# inv_pendulum.net
KiCad netlist of a schematic drawn in EAGLE
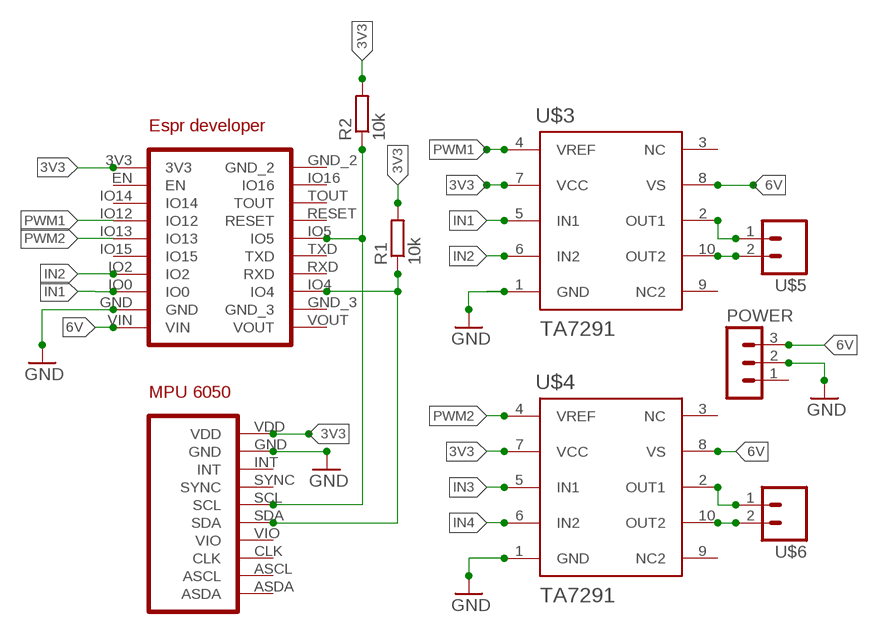
[diagram p0: schematic, sheet 1]

(export (version "E")
  (design (tool "Eeschema 10.0.6"))
  (components
    (comp (ref "POWER")
      (value "MA03-1")
      (footprint "eagle-import:MA03-1")
      (libsource (lib "eagle-import") (part "MA03-1"))
    )
    (comp (ref "R1")
      (value "10k")
      (footprint "eagle-import:0204_7")
      (libsource (lib "eagle-import") (part "R-EU_0204/7"))
    )
    (comp (ref "R2")
      (value "10k")
      (footprint "eagle-import:0204_7")
      (libsource (lib "eagle-import") (part "R-EU_0204/7"))
    )
    (comp (ref "U$1")
      (value "MPU6050")
      (footprint "eagle-import:MPU6050")
      (libsource (lib "eagle-import") (part "MPU6050"))
    )
    (comp (ref "U$2")
      (value "ESPR_DEVELOPER")
      (footprint "eagle-import:ESPR_DEV")
      (libsource (lib "eagle-import") (part "ESPR_DEVELOPER"))
    )
    (comp (ref "U$3")
      (value "TA7291")
      (footprint "eagle-import:HSIP10")
      (libsource (lib "eagle-import") (part "TA7291"))
    )
    (comp (ref "U$4")
      (value "TA7291")
      (footprint "eagle-import:HSIP10")
      (libsource (lib "eagle-import") (part "TA7291"))
    )
    (comp (ref "U$5")
      (value "M02LOCK_LONGPADS")
      (footprint "eagle-import:1X02_LOCK_LONGPADS")
      (libsource (lib "eagle-import") (part "M02LOCK_LONGPADS"))
    )
    (comp (ref "U$6")
      (value "M02LOCK_LONGPADS")
      (footprint "eagle-import:1X02_LOCK_LONGPADS")
      (libsource (lib "eagle-import") (part "M02LOCK_LONGPADS"))
    )
  )
  (nets
    (net (code "1") (name "3V3") (class "Default")
      (node (ref "R1") (pin "2") (pinfunction "2_2") (pintype "passive"))
      (node (ref "R2") (pin "2") (pinfunction "2_2") (pintype "passive"))
      (node (ref "U$1") (pin "VDD") (pinfunction "VDD_VDD") (pintype "bidirectional"))
      (node (ref "U$2") (pin "3V3") (pinfunction "3V3_3V3") (pintype "bidirectional"))
      (node (ref "U$3") (pin "7") (pinfunction "VCC_7") (pintype "bidirectional"))
      (node (ref "U$4") (pin "7") (pinfunction "VCC_7") (pintype "bidirectional"))
    )
    (net (code "2") (name "6V") (class "Default")
      (node (ref "POWER") (pin "3") (pinfunction "3_3") (pintype "passive"))
      (node (ref "U$2") (pin "VIN") (pinfunction "VIN_VIN") (pintype "bidirectional"))
      (node (ref "U$3") (pin "8") (pinfunction "VS_8") (pintype "bidirectional"))
      (node (ref "U$4") (pin "8") (pinfunction "VS_8") (pintype "bidirectional"))
    )
    (net (code "3") (name "GND") (class "Default")
      (node (ref "POWER") (pin "2") (pinfunction "2_2") (pintype "passive"))
      (node (ref "U$1") (pin "GND") (pinfunction "GND_GND") (pintype "bidirectional"))
      (node (ref "U$2") (pin "GND") (pinfunction "GND_GND") (pintype "bidirectional"))
      (node (ref "U$3") (pin "1") (pinfunction "GND_1") (pintype "bidirectional"))
      (node (ref "U$4") (pin "1") (pinfunction "GND_1") (pintype "bidirectional"))
    )
    (net (code "4") (name "IN1") (class "Default")
      (node (ref "U$2") (pin "IO0") (pinfunction "IO0_IO0") (pintype "bidirectional"))
      (node (ref "U$3") (pin "5") (pinfunction "IN1_5") (pintype "bidirectional"))
    )
    (net (code "5") (name "IN2") (class "Default")
      (node (ref "U$2") (pin "IO2") (pinfunction "IO2_IO2") (pintype "bidirectional"))
      (node (ref "U$3") (pin "6") (pinfunction "IN2_6") (pintype "bidirectional"))
    )
    (net (code "6") (name "IN3") (class "Default")
      (node (ref "U$4") (pin "5") (pinfunction "IN1_5") (pintype "bidirectional"))
    )
    (net (code "7") (name "IN4") (class "Default")
      (node (ref "U$4") (pin "6") (pinfunction "IN2_6") (pintype "bidirectional"))
    )
    (net (code "8") (name "Net-(R1-Pad1)") (class "Default")
      (node (ref "R1") (pin "1") (pinfunction "1_1") (pintype "passive"))
      (node (ref "U$1") (pin "SDA") (pinfunction "SDA_SDA") (pintype "bidirectional"))
      (node (ref "U$2") (pin "IO4") (pinfunction "IO4_IO4") (pintype "bidirectional"))
    )
    (net (code "9") (name "Net-(R2-Pad1)") (class "Default")
      (node (ref "R2") (pin "1") (pinfunction "1_1") (pintype "passive"))
      (node (ref "U$1") (pin "SCL") (pinfunction "SCL_SCL") (pintype "bidirectional"))
      (node (ref "U$2") (pin "IO5") (pinfunction "IO5_IO5") (pintype "bidirectional"))
    )
    (net (code "10") (name "Net-(U$3-OUT1)") (class "Default")
      (node (ref "U$3") (pin "2") (pinfunction "OUT1_2") (pintype "bidirectional"))
      (node (ref "U$5") (pin "1") (pinfunction "1_1") (pintype "passive"))
    )
    (net (code "11") (name "Net-(U$3-OUT2)") (class "Default")
      (node (ref "U$3") (pin "10") (pinfunction "OUT2_10") (pintype "bidirectional"))
      (node (ref "U$5") (pin "2") (pinfunction "2_2") (pintype "passive"))
    )
    (net (code "12") (name "Net-(U$4-OUT1)") (class "Default")
      (node (ref "U$4") (pin "2") (pinfunction "OUT1_2") (pintype "bidirectional"))
      (node (ref "U$6") (pin "1") (pinfunction "1_1") (pintype "passive"))
    )
    (net (code "13") (name "Net-(U$4-OUT2)") (class "Default")
      (node (ref "U$4") (pin "10") (pinfunction "OUT2_10") (pintype "bidirectional"))
      (node (ref "U$6") (pin "2") (pinfunction "2_2") (pintype "passive"))
    )
    (net (code "14") (name "PWM1") (class "Default")
      (node (ref "U$2") (pin "IO12") (pinfunction "IO12_IO12") (pintype "bidirectional"))
      (node (ref "U$3") (pin "4") (pinfunction "VREF_4") (pintype "bidirectional"))
    )
    (net (code "15") (name "PWM2") (class "Default")
      (node (ref "U$2") (pin "IO13") (pinfunction "IO13_IO13") (pintype "bidirectional"))
      (node (ref "U$4") (pin "4") (pinfunction "VREF_4") (pintype "bidirectional"))
    )
    (net (code "16") (name "unconnected-(POWER-Pad1)") (class "Default")
      (node (ref "POWER") (pin "1") (pinfunction "1_1") (pintype "passive"))
    )
    (net (code "17") (name "unconnected-(U$1-PadASCL)") (class "Default")
      (node (ref "U$1") (pin "ASCL") (pinfunction "ASCL_ASCL") (pintype "bidirectional"))
    )
    (net (code "18") (name "unconnected-(U$1-PadASDA)") (class "Default")
      (node (ref "U$1") (pin "ASDA") (pinfunction "ASDA_ASDA") (pintype "bidirectional"))
    )
    (net (code "19") (name "unconnected-(U$1-PadCLK)") (class "Default")
      (node (ref "U$1") (pin "CLK") (pinfunction "CLK_CLK") (pintype "bidirectional"))
    )
    (net (code "20") (name "unconnected-(U$1-PadINT)") (class "Default")
      (node (ref "U$1") (pin "INT") (pinfunction "INT_INT") (pintype "bidirectional"))
    )
    (net (code "21") (name "unconnected-(U$1-PadSYNC)") (class "Default")
      (node (ref "U$1") (pin "SYNC") (pinfunction "SYNC_SYNC") (pintype "bidirectional"))
    )
    (net (code "22") (name "unconnected-(U$1-PadVIO)") (class "Default")
      (node (ref "U$1") (pin "VIO") (pinfunction "VIO_VIO") (pintype "bidirectional"))
    )
    (net (code "23") (name "unconnected-(U$2-PadEN)") (class "Default")
      (node (ref "U$2") (pin "EN") (pinfunction "EN_EN") (pintype "bidirectional"))
    )
    (net (code "24") (name "unconnected-(U$2-PadGND_2)") (class "Default")
      (node (ref "U$2") (pin "GND_2") (pinfunction "GND_2_GND_2") (pintype "bidirectional"))
    )
    (net (code "25") (name "unconnected-(U$2-PadGND_3)") (class "Default")
      (node (ref "U$2") (pin "GND_3") (pinfunction "GND_3_GND_3") (pintype "bidirectional"))
    )
    (net (code "26") (name "unconnected-(U$2-PadIO14)") (class "Default")
      (node (ref "U$2") (pin "IO14") (pinfunction "IO14_IO14") (pintype "bidirectional"))
    )
    (net (code "27") (name "unconnected-(U$2-PadIO15)") (class "Default")
      (node (ref "U$2") (pin "IO15") (pinfunction "IO15_IO15") (pintype "bidirectional"))
    )
    (net (code "28") (name "unconnected-(U$2-PadIO16)") (class "Default")
      (node (ref "U$2") (pin "IO16") (pinfunction "IO16_IO16") (pintype "bidirectional"))
    )
    (net (code "29") (name "unconnected-(U$2-PadRESET)") (class "Default")
      (node (ref "U$2") (pin "RESET") (pinfunction "RESET_RESET") (pintype "bidirectional"))
    )
    (net (code "30") (name "unconnected-(U$2-PadRXD)") (class "Default")
      (node (ref "U$2") (pin "RXD") (pinfunction "RXD_RXD") (pintype "bidirectional"))
    )
    (net (code "31") (name "unconnected-(U$2-PadTOUT)") (class "Default")
      (node (ref "U$2") (pin "TOUT") (pinfunction "TOUT_TOUT") (pintype "bidirectional"))
    )
    (net (code "32") (name "unconnected-(U$2-PadTXD)") (class "Default")
      (node (ref "U$2") (pin "TXD") (pinfunction "TXD_TXD") (pintype "bidirectional"))
    )
    (net (code "33") (name "unconnected-(U$2-PadVOUT)") (class "Default")
      (node (ref "U$2") (pin "VOUT") (pinfunction "VOUT_VOUT") (pintype "bidirectional"))
    )
    (net (code "34") (name "unconnected-(U$3-NC-Pad3)") (class "Default")
      (node (ref "U$3") (pin "3") (pinfunction "NC_3") (pintype "bidirectional"))
    )
    (net (code "35") (name "unconnected-(U$3-NC2-Pad9)") (class "Default")
      (node (ref "U$3") (pin "9") (pinfunction "NC2_9") (pintype "bidirectional"))
    )
    (net (code "36") (name "unconnected-(U$4-NC-Pad3)") (class "Default")
      (node (ref "U$4") (pin "3") (pinfunction "NC_3") (pintype "bidirectional"))
    )
    (net (code "37") (name "unconnected-(U$4-NC2-Pad9)") (class "Default")
      (node (ref "U$4") (pin "9") (pinfunction "NC2_9") (pintype "bidirectional"))
    )
  )
)
